# STLINK_V3EC.net
KiCad netlist of a schematic drawn in Altium Designer
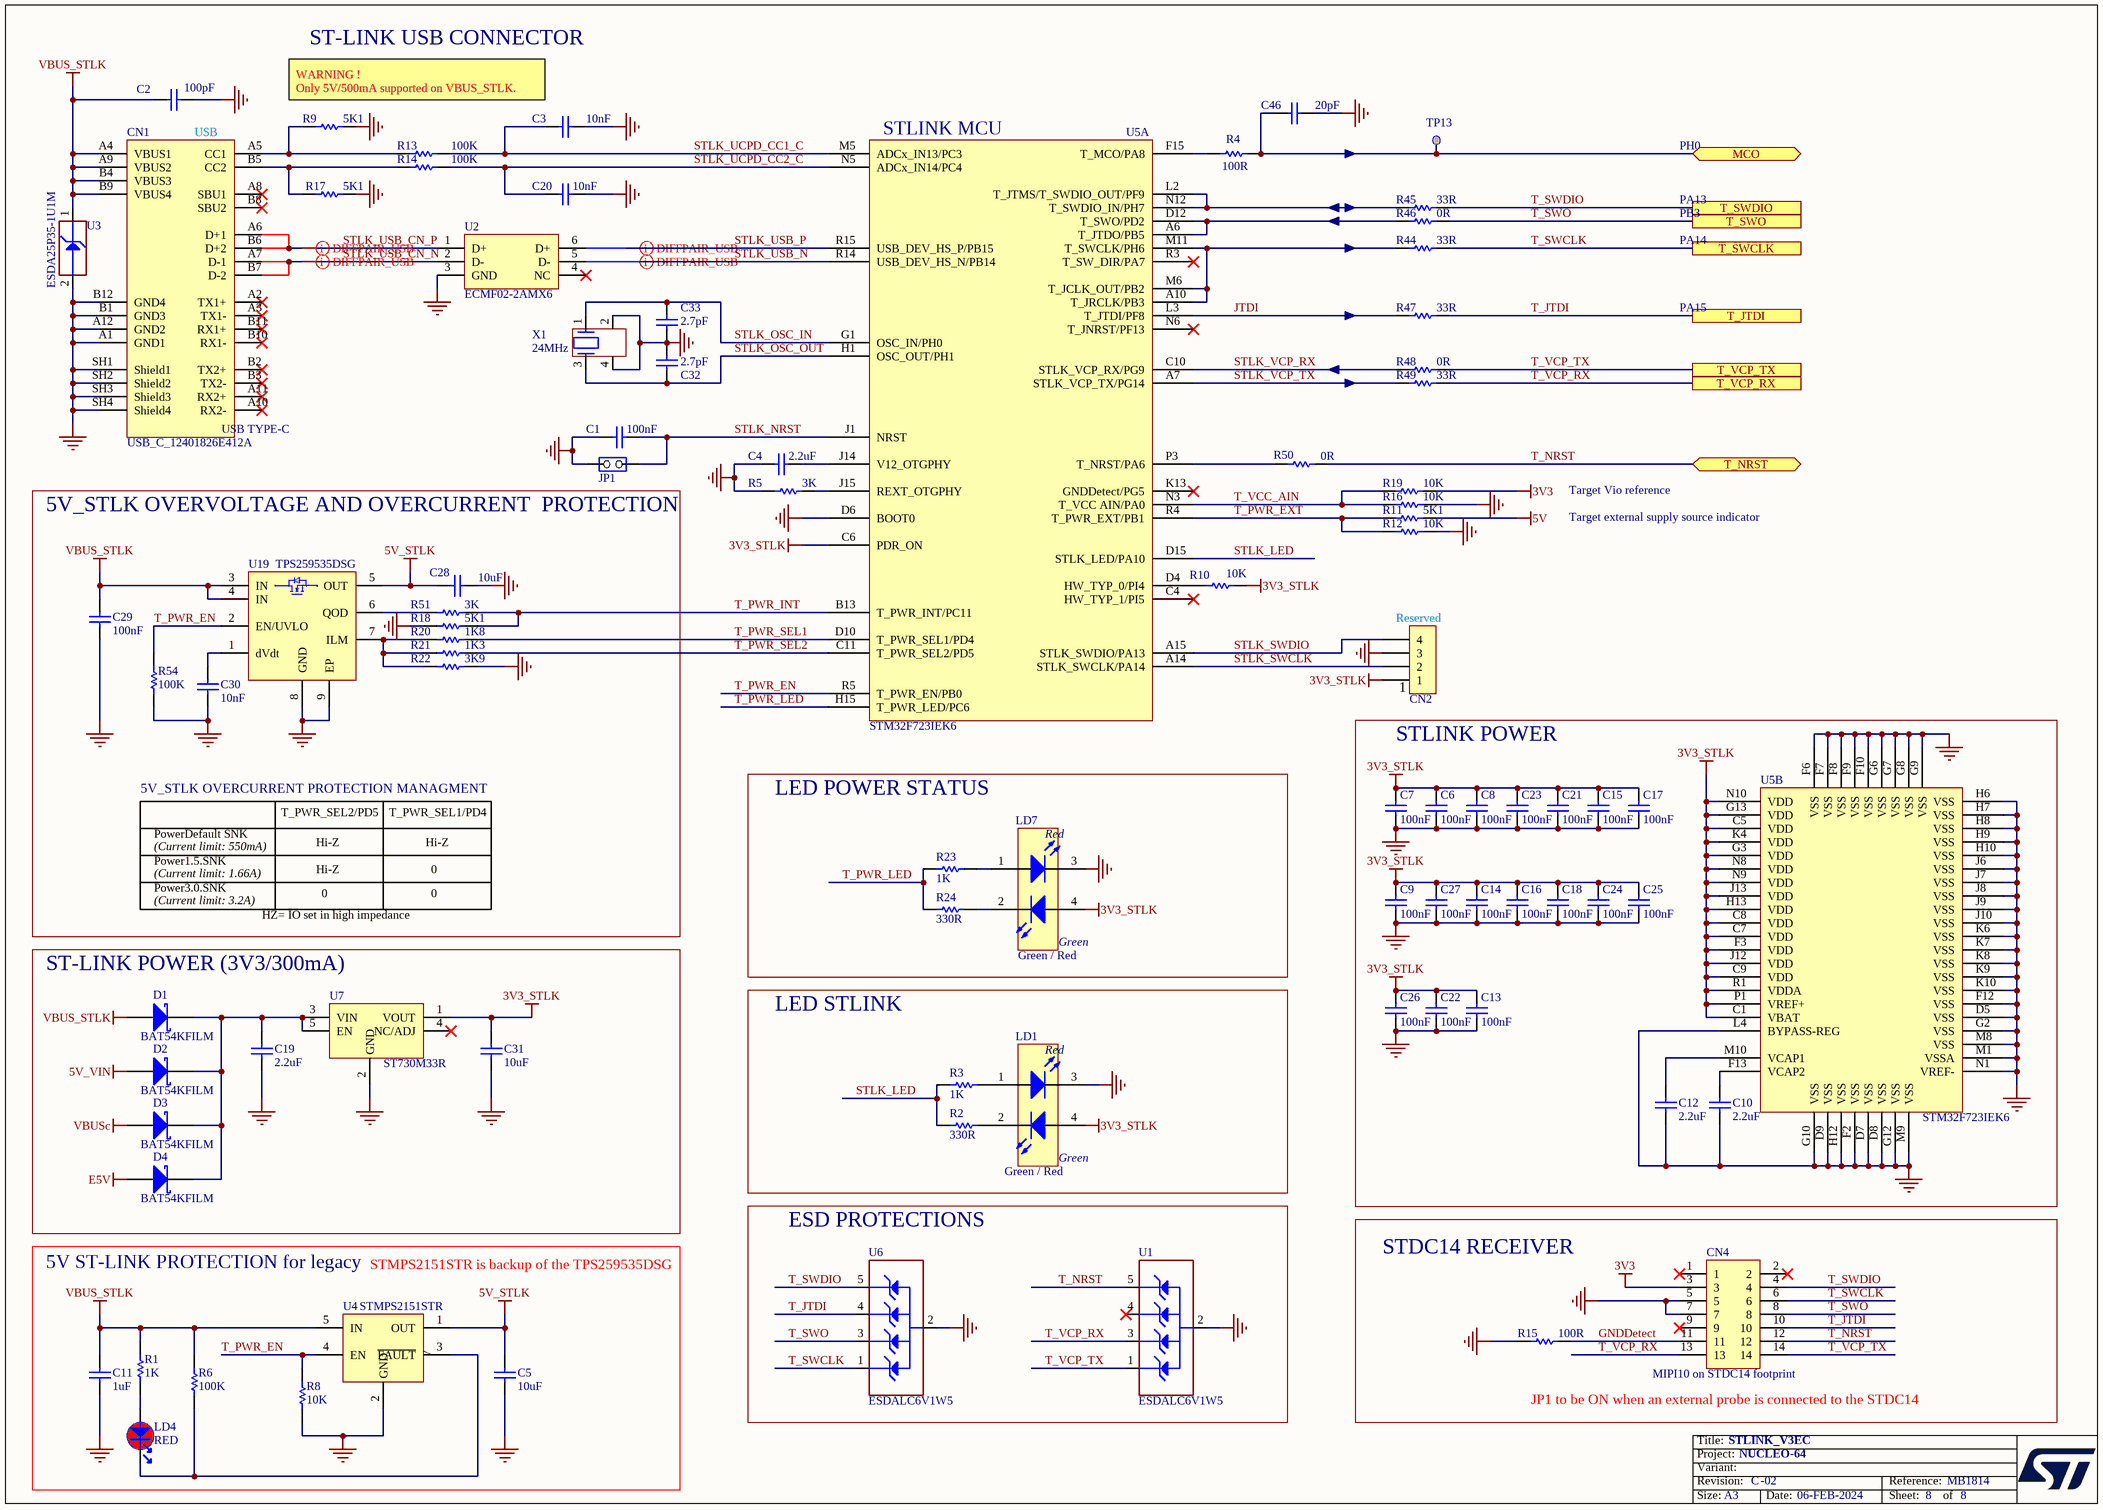
[diagram p0: STLINK_V3EC.SchDoc]

(export (version "E")
  (design (tool "Eeschema 10.0.6"))
  (components
    (comp (ref "C1")
      (value "100nF")
      (footprint "C0402")
      (description "Capacitor, MLCC, 100nF, 16V, X7R, 10%, 0402, T=0.5mm")
      (fields
        (field (name "INTERNAL_PART_NUMBER") "MCD-00006")
        (field (name "MANUFACTURER_PART_NUMBER") "CC0402KRX7R7BB104")
        (field (name "PROVIDED_BY") "SUBCO")
      )
      (libsource (lib "MCD_PARTS_database") (part "Capacitor"))
    )
    (comp (ref "C2")
      (value "100pF")
      (footprint "C0402")
      (description "Capacitor, MLCC, 100pF, 50V, NPO, +/-5%, 0402, T=0.5mm")
      (fields (field (name "INTERNAL_PART_NUMBER") "MCD-00205") (field (name "MANUFACTURER") "YAGEO"))
      (libsource (lib "MCD_PARTS_database") (part "Capacitor"))
    )
    (comp (ref "C3")
      (value "10nF")
      (footprint "C0402")
      (description "Capacitor, MLCC, 10nF, 50V, X7R, +/-10%, 0402, T=0.5mm")
      (fields (field (name "INTERNAL_PART_NUMBER") "MCD-02198") (field (name "MANUFACTURER") "YAGEO"))
      (libsource (lib "MCD_PARTS_database") (part "Capacitor"))
    )
    (comp (ref "C4")
      (value "2.2uF")
      (footprint "C0402")
      (description "Capacitor, MLCC, 2.2uF, 6.3V, X5R, +/-10%, 0402, T=0.5mm")
      (fields (field (name "INTERNAL_PART_NUMBER") "MCD-02606") (field (name "MANUFACTURER") "YAGEO"))
      (libsource (lib "MCD_PARTS_database") (part "Capacitor"))
    )
    (comp (ref "C5")
      (value "10uF")
      (footprint "C0603")
      (description "Capacitor, MLCC, 10uF, 10V, X5R, +/-10%, 0603, T=0.8mm")
      (fields (field (name "INTERNAL_PART_NUMBER") "MCD-00099") (field (name "MANUFACTURER") "MURATA"))
      (libsource (lib "MCD_PARTS_database") (part "Capacitor"))
    )
    (comp (ref "C6")
      (value "100nF")
      (footprint "C0402")
      (description "Capacitor, MLCC, 100nF, 16V, X7R, 10%, 0402, T=0.5mm")
      (fields
        (field (name "INTERNAL_PART_NUMBER") "MCD-00006")
        (field (name "MANUFACTURER_PART_NUMBER") "CC0402KRX7R7BB104")
        (field (name "PROVIDED_BY") "SUBCO")
      )
      (libsource (lib "MCD_PARTS_database") (part "Capacitor"))
    )
    (comp (ref "C7")
      (value "100nF")
      (footprint "C0402")
      (description "Capacitor, MLCC, 100nF, 16V, X7R, 10%, 0402, T=0.5mm")
      (fields
        (field (name "INTERNAL_PART_NUMBER") "MCD-00006")
        (field (name "MANUFACTURER_PART_NUMBER") "CC0402KRX7R7BB104")
        (field (name "PROVIDED_BY") "SUBCO")
      )
      (libsource (lib "MCD_PARTS_database") (part "Capacitor"))
    )
    (comp (ref "C8")
      (value "100nF")
      (footprint "C0402")
      (description "Capacitor, MLCC, 100nF, 16V, X7R, 10%, 0402, T=0.5mm")
      (fields
        (field (name "INTERNAL_PART_NUMBER") "MCD-00006")
        (field (name "MANUFACTURER_PART_NUMBER") "CC0402KRX7R7BB104")
        (field (name "PROVIDED_BY") "SUBCO")
      )
      (libsource (lib "MCD_PARTS_database") (part "Capacitor"))
    )
    (comp (ref "C9")
      (value "100nF")
      (footprint "C0402")
      (description "Capacitor, MLCC, 100nF, 16V, X7R, 10%, 0402, T=0.5mm")
      (fields
        (field (name "INTERNAL_PART_NUMBER") "MCD-00006")
        (field (name "MANUFACTURER_PART_NUMBER") "CC0402KRX7R7BB104")
        (field (name "PROVIDED_BY") "SUBCO")
      )
      (libsource (lib "MCD_PARTS_database") (part "Capacitor"))
    )
    (comp (ref "C10")
      (value "2.2uF")
      (footprint "C0402")
      (description "Capacitor, MLCC, 2.2uF, 6.3V, X5R, +/-10%, 0402, T=0.5mm")
      (fields (field (name "INTERNAL_PART_NUMBER") "MCD-02606") (field (name "MANUFACTURER") "YAGEO"))
      (libsource (lib "MCD_PARTS_database") (part "Capacitor"))
    )
    (comp (ref "C11")
      (value "1uF")
      (footprint "C0603")
      (description "Capacitor, MLCC, 1uF, 16V, X5R, 10%, 0603, T=0,8mm")
      (fields
        (field (name "INTERNAL_PART_NUMBER") "MCD-00010")
        (field (name "MANUFACTURER_PART_NUMBER") "CC0603KRX5R7BB105")
        (field (name "PROVIDED_BY") "SUBCO")
      )
      (libsource (lib "MCD_PARTS_database") (part "Capacitor"))
    )
    (comp (ref "C12")
      (value "2.2uF")
      (footprint "C0402")
      (description "Capacitor, MLCC, 2.2uF, 6.3V, X5R, +/-10%, 0402, T=0.5mm")
      (fields (field (name "INTERNAL_PART_NUMBER") "MCD-02606") (field (name "MANUFACTURER") "YAGEO"))
      (libsource (lib "MCD_PARTS_database") (part "Capacitor"))
    )
    (comp (ref "C13")
      (value "100nF")
      (footprint "C0402")
      (description "Capacitor, MLCC, 100nF, 16V, X7R, 10%, 0402, T=0.5mm")
      (fields
        (field (name "INTERNAL_PART_NUMBER") "MCD-00006")
        (field (name "MANUFACTURER_PART_NUMBER") "CC0402KRX7R7BB104")
        (field (name "PROVIDED_BY") "SUBCO")
      )
      (libsource (lib "MCD_PARTS_database") (part "Capacitor"))
    )
    (comp (ref "C14")
      (value "100nF")
      (footprint "C0402")
      (description "Capacitor, MLCC, 100nF, 16V, X7R, 10%, 0402, T=0.5mm")
      (fields
        (field (name "INTERNAL_PART_NUMBER") "MCD-00006")
        (field (name "MANUFACTURER_PART_NUMBER") "CC0402KRX7R7BB104")
        (field (name "PROVIDED_BY") "SUBCO")
      )
      (libsource (lib "MCD_PARTS_database") (part "Capacitor"))
    )
    (comp (ref "C15")
      (value "100nF")
      (footprint "C0402")
      (description "Capacitor, MLCC, 100nF, 16V, X7R, 10%, 0402, T=0.5mm")
      (fields
        (field (name "INTERNAL_PART_NUMBER") "MCD-00006")
        (field (name "MANUFACTURER_PART_NUMBER") "CC0402KRX7R7BB104")
        (field (name "PROVIDED_BY") "SUBCO")
      )
      (libsource (lib "MCD_PARTS_database") (part "Capacitor"))
    )
    (comp (ref "C16")
      (value "100nF")
      (footprint "C0402")
      (description "Capacitor, MLCC, 100nF, 16V, X7R, 10%, 0402, T=0.5mm")
      (fields
        (field (name "INTERNAL_PART_NUMBER") "MCD-00006")
        (field (name "MANUFACTURER_PART_NUMBER") "CC0402KRX7R7BB104")
        (field (name "PROVIDED_BY") "SUBCO")
      )
      (libsource (lib "MCD_PARTS_database") (part "Capacitor"))
    )
    (comp (ref "C17")
      (value "100nF")
      (footprint "C0402")
      (description "Capacitor, MLCC, 100nF, 16V, X7R, 10%, 0402, T=0.5mm")
      (fields
        (field (name "INTERNAL_PART_NUMBER") "MCD-00006")
        (field (name "MANUFACTURER_PART_NUMBER") "CC0402KRX7R7BB104")
        (field (name "PROVIDED_BY") "SUBCO")
      )
      (libsource (lib "MCD_PARTS_database") (part "Capacitor"))
    )
    (comp (ref "C18")
      (value "100nF")
      (footprint "C0402")
      (description "Capacitor, MLCC, 100nF, 16V, X7R, 10%, 0402, T=0.5mm")
      (fields
        (field (name "INTERNAL_PART_NUMBER") "MCD-00006")
        (field (name "MANUFACTURER_PART_NUMBER") "CC0402KRX7R7BB104")
        (field (name "PROVIDED_BY") "SUBCO")
      )
      (libsource (lib "MCD_PARTS_database") (part "Capacitor"))
    )
    (comp (ref "C19")
      (value "2.2uF")
      (footprint "C0805")
      (description "Capacitor, MLCC, 2.2uF, 25V, X7R, +/-10%, 0805, T=1,25mm")
      (fields
        (field (name "INTERNAL_PART_NUMBER") "MCD-02372")
        (field (name "MANUFACTURER_PART_NUMBER") "GRM21BR71E225KE11L")
        (field (name "PROVIDED_BY") "SUBCO")
      )
      (libsource (lib "MCD_PARTS_database") (part "Capacitor"))
    )
    (comp (ref "C20")
      (value "10nF")
      (footprint "C0402")
      (description "Capacitor, MLCC, 10nF, 50V, X7R, +/-10%, 0402, T=0.5mm")
      (fields (field (name "INTERNAL_PART_NUMBER") "MCD-02198") (field (name "MANUFACTURER") "YAGEO"))
      (libsource (lib "MCD_PARTS_database") (part "Capacitor"))
    )
    (comp (ref "C21")
      (value "100nF")
      (footprint "C0402")
      (description "Capacitor, MLCC, 100nF, 16V, X7R, 10%, 0402, T=0.5mm")
      (fields
        (field (name "INTERNAL_PART_NUMBER") "MCD-00006")
        (field (name "MANUFACTURER_PART_NUMBER") "CC0402KRX7R7BB104")
        (field (name "PROVIDED_BY") "SUBCO")
      )
      (libsource (lib "MCD_PARTS_database") (part "Capacitor"))
    )
    (comp (ref "C22")
      (value "100nF")
      (footprint "C0402")
      (description "Capacitor, MLCC, 100nF, 16V, X7R, 10%, 0402, T=0.5mm")
      (fields
        (field (name "INTERNAL_PART_NUMBER") "MCD-00006")
        (field (name "MANUFACTURER_PART_NUMBER") "CC0402KRX7R7BB104")
        (field (name "PROVIDED_BY") "SUBCO")
      )
      (libsource (lib "MCD_PARTS_database") (part "Capacitor"))
    )
    (comp (ref "C23")
      (value "100nF")
      (footprint "C0402")
      (description "Capacitor, MLCC, 100nF, 16V, X7R, 10%, 0402, T=0.5mm")
      (fields
        (field (name "INTERNAL_PART_NUMBER") "MCD-00006")
        (field (name "MANUFACTURER_PART_NUMBER") "CC0402KRX7R7BB104")
        (field (name "PROVIDED_BY") "SUBCO")
      )
      (libsource (lib "MCD_PARTS_database") (part "Capacitor"))
    )
    (comp (ref "C24")
      (value "100nF")
      (footprint "C0402")
      (description "Capacitor, MLCC, 100nF, 16V, X7R, 10%, 0402, T=0.5mm")
      (fields
        (field (name "INTERNAL_PART_NUMBER") "MCD-00006")
        (field (name "MANUFACTURER_PART_NUMBER") "CC0402KRX7R7BB104")
        (field (name "PROVIDED_BY") "SUBCO")
      )
      (libsource (lib "MCD_PARTS_database") (part "Capacitor"))
    )
    (comp (ref "C25")
      (value "100nF")
      (footprint "C0402")
      (description "Capacitor, MLCC, 100nF, 16V, X7R, 10%, 0402, T=0.5mm")
      (fields
        (field (name "INTERNAL_PART_NUMBER") "MCD-00006")
        (field (name "MANUFACTURER_PART_NUMBER") "CC0402KRX7R7BB104")
        (field (name "PROVIDED_BY") "SUBCO")
      )
      (libsource (lib "MCD_PARTS_database") (part "Capacitor"))
    )
    (comp (ref "C26")
      (value "100nF")
      (footprint "C0402")
      (description "Capacitor, MLCC, 100nF, 16V, X7R, 10%, 0402, T=0.5mm")
      (fields
        (field (name "INTERNAL_PART_NUMBER") "MCD-00006")
        (field (name "MANUFACTURER_PART_NUMBER") "CC0402KRX7R7BB104")
        (field (name "PROVIDED_BY") "SUBCO")
      )
      (libsource (lib "MCD_PARTS_database") (part "Capacitor"))
    )
    (comp (ref "C27")
      (value "100nF")
      (footprint "C0402")
      (description "Capacitor, MLCC, 100nF, 16V, X7R, 10%, 0402, T=0.5mm")
      (fields
        (field (name "INTERNAL_PART_NUMBER") "MCD-00006")
        (field (name "MANUFACTURER_PART_NUMBER") "CC0402KRX7R7BB104")
        (field (name "PROVIDED_BY") "SUBCO")
      )
      (libsource (lib "MCD_PARTS_database") (part "Capacitor"))
    )
    (comp (ref "C28")
      (value "10uF")
      (footprint "C0603")
      (description "Capacitor, MLCC, 10uF, 10V, X5R, +/-10%, 0603, T=0.8mm")
      (fields (field (name "INTERNAL_PART_NUMBER") "MCD-00099") (field (name "MANUFACTURER") "MURATA"))
      (libsource (lib "MCD_PARTS_database") (part "Capacitor"))
    )
    (comp (ref "C29")
      (value "100nF")
      (footprint "C0402")
      (description "Capacitor, MLCC, 100nF, 25V, X7R, +/-10%, 0402, T=0.5mm")
      (fields (field (name "INTERNAL_PART_NUMBER") "MCD-02355") (field (name "MANUFACTURER") "WALSIN"))
      (libsource (lib "MCD_PARTS_database") (part "Capacitor"))
    )
    (comp (ref "C30")
      (value "10nF")
      (footprint "C0402")
      (description "Capacitor, MLCC, 10nF, 50V, X7R, +/-10%, 0402, T=0.5mm")
      (fields (field (name "INTERNAL_PART_NUMBER") "MCD-02198") (field (name "MANUFACTURER") "YAGEO"))
      (libsource (lib "MCD_PARTS_database") (part "Capacitor"))
    )
    (comp (ref "C31")
      (value "10uF")
      (footprint "C0603")
      (description "Capacitor, MLCC, 10uF, 10V, X5R, +/-10%, 0603, T=0.8mm")
      (fields (field (name "INTERNAL_PART_NUMBER") "MCD-00099") (field (name "MANUFACTURER") "MURATA"))
      (libsource (lib "MCD_PARTS_database") (part "Capacitor"))
    )
    (comp (ref "C32")
      (value "2.7pF")
      (footprint "C0402")
      (description "Capacitor, MLCC, 2.7pF, 50V, NPO, +/-0.1pF, 0402, T=0.5mm")
      (fields (field (name "INTERNAL_PART_NUMBER") "MCD-01774") (field (name "MANUFACTURER") "YAGEO"))
      (libsource (lib "MCD_PARTS_database") (part "Capacitor"))
    )
    (comp (ref "C33")
      (value "2.7pF")
      (footprint "C0402")
      (description "Capacitor, MLCC, 2.7pF, 50V, NPO, +/-0.1pF, 0402, T=0.5mm")
      (fields (field (name "INTERNAL_PART_NUMBER") "MCD-01774") (field (name "MANUFACTURER") "YAGEO"))
      (libsource (lib "MCD_PARTS_database") (part "Capacitor"))
    )
    (comp (ref "C46")
      (value "20pF")
      (footprint "C0402")
      (description "Capacitor, MLCC, 20pF, 50V, NPO, +/- 5%, 0402, T=0.5mm")
      (fields (field (name "INTERNAL_PART_NUMBER") "MCD-00016") (field (name "MANUFACTURER") "YAGEO"))
      (libsource (lib "MCD_PARTS_database") (part "Capacitor"))
    )
    (comp (ref "CN1")
      (value "USB_C_12401826E412A")
      (footprint "CON_USB-TYPEC_AMPHENOL_12401826E412A")
      (description "USB_TypeC, 24 pins, RA, SMD, T=2.96mm")
      (fields (field (name "INTERNAL_PART_NUMBER") "MCD-03232") (field (name "MANUFACTURER") "AMPHENOL ICC"))
      (libsource (lib "MCD_PARTS_database") (part "USB_TYPE_C_Receptacle"))
    )
    (comp (ref "CN2")
      (value "Header 4x1")
      (footprint "CON_SAMTEC_TSW-104-07-G-S")
      (description "Header, 4x1, 2,54mm, VR, TH, Height 5.84mm/2.54mm")
      (fields
        (field (name "INTERNAL_PART_NUMBER") "MCD-00029")
        (field (name "MANUFACTURER_PART_NUMBER") "TSW-104-07-x-S")
        (field (name "PROVIDED_BY") "SUBCO")
      )
      (libsource (lib "MCD_PARTS_database") (part "Header 4x1"))
    )
    (comp (ref "CN4")
      (value "Header 7x2")
      (footprint "CON_STDC14_Receiver_MEDIUM_WITH_MIPI10_3D")
      (description "Header, 5x2, 1.27mm, VR, SMD, T=5.97mm/3.05mm")
      (fields (field (name "INTERNAL_PART_NUMBER") "MCD-01226") (field (name "MANUFACTURER") "SAMTEC"))
      (libsource (lib "MCD_PARTS_database") (part "Header 7x2"))
    )
    (comp (ref "D1")
      (value "BAT54KFILM")
      (footprint "DIO_SOD523_1A_2K")
      (description "Small signal Schottky diodes")
      (fields (field (name "INTERNAL_PART_NUMBER") "MCD-01677") (field (name "BMS_PART_NUMBER") "9151123"))
      (libsource (lib "MCD_PARTS_database") (part "SCHOTTKY_1A_2K"))
    )
    (comp (ref "D2")
      (value "BAT54KFILM")
      (footprint "DIO_SOD523_1A_2K")
      (description "Small signal Schottky diodes")
      (fields (field (name "INTERNAL_PART_NUMBER") "MCD-01677") (field (name "BMS_PART_NUMBER") "9151123"))
      (libsource (lib "MCD_PARTS_database") (part "SCHOTTKY_1A_2K"))
    )
    (comp (ref "D3")
      (value "BAT54KFILM")
      (footprint "DIO_SOD523_1A_2K")
      (description "Small signal Schottky diodes")
      (fields (field (name "INTERNAL_PART_NUMBER") "MCD-01677") (field (name "BMS_PART_NUMBER") "9151123"))
      (libsource (lib "MCD_PARTS_database") (part "SCHOTTKY_1A_2K"))
    )
    (comp (ref "D4")
      (value "BAT54KFILM")
      (footprint "DIO_SOD523_1A_2K")
      (description "Small signal Schottky diodes")
      (fields (field (name "INTERNAL_PART_NUMBER") "MCD-01677") (field (name "BMS_PART_NUMBER") "9151123"))
      (libsource (lib "MCD_PARTS_database") (part "SCHOTTKY_1A_2K"))
    )
    (comp (ref "JP1")
      (value "Jumper_Header 2x1")
      (footprint "CON_SAMTEC_TSW-102-07-G-S")
      (description "Header, 2x1, 2,54mm, VR, TH, Height 5.84mm/2.54mm")
      (fields (field (name "INTERNAL_PART_NUMBER") "MCD-00045") (field (name "MANUFACTURER") "SAMTEC"))
      (libsource (lib "MCD_PARTS_database") (part "Jumper_Header 2x1"))
    )
    (comp (ref "LD1")
      (value "Green / Red")
      (footprint "LED_BI-GR_WE-150141SV73110")
      (description "LED Bicolor, Green/Red, 2V, 20mA,  4-PLCC")
      (fields
        (field (name "INTERNAL_PART_NUMBER") "MCD-02631")
        (field (name "MANUFACTURER") "WURTH ELEKTRONIK")
      )
      (libsource (lib "MCD_PARTS_database") (part "LED_BICOLOR"))
    )
    (comp (ref "LD4")
      (value "RED")
      (footprint "LED_0603_VISHAY_VLMS1300-GS08_RED_1A2K_H0P8")
      (description "LED Red, 0603 SMD, 2V Forward Voltage")
      (fields
        (field (name "INTERNAL_PART_NUMBER") "MCD-00587")
        (field (name "MANUFACTURER_PART_NUMBER") "VLMS1300-GS08")
        (field (name "PROVIDED_BY") "SUBCO")
      )
      (libsource (lib "MCD_PARTS_database") (part "LED_red"))
    )
    (comp (ref "LD7")
      (value "Green / Red")
      (footprint "LED_BI-GR_WE-150141SV73110")
      (description "LED Bicolor, Green/Red, 2V, 20mA,  4-PLCC")
      (fields
        (field (name "INTERNAL_PART_NUMBER") "MCD-02631")
        (field (name "MANUFACTURER") "WURTH ELEKTRONIK")
      )
      (libsource (lib "MCD_PARTS_database") (part "LED_BICOLOR"))
    )
    (comp (ref "R1")
      (value "1K")
      (footprint "R0402")
      (description "Resistor,1K,0402,1%,1/16W")
      (fields
        (field (name "INTERNAL_PART_NUMBER") "MCD-00061")
        (field (name "MANUFACTURER_PART_NUMBER") "RC0402FR-071KL")
        (field (name "PROVIDED_BY") "SUBCO")
      )
      (libsource (lib "MCD_PARTS_database") (part "Resistor"))
    )
    (comp (ref "R2")
      (value "330R")
      (footprint "R0402")
      (description "Resistor, 330R, 0402, +/-1%, 1/16W")
      (fields (field (name "INTERNAL_PART_NUMBER") "MCD-00062") (field (name "MANUFACTURER") "YAGEO"))
      (libsource (lib "MCD_PARTS_database") (part "Resistor"))
    )
    (comp (ref "R3")
      (value "1K")
      (footprint "R0402")
      (description "Resistor, 1K, 0402, +/-0.1%, 1/16W, +/-25ppm/°C")
      (fields (field (name "INTERNAL_PART_NUMBER") "MCD-02665") (field (name "MANUFACTURER") "YAGEO"))
      (libsource (lib "MCD_PARTS_database") (part "Resistor"))
    )
    (comp (ref "R4")
      (value "100R")
      (footprint "R0402")
      (description "Resistor, 100R, 0402, +/- 1%, 1/16W")
      (fields (field (name "INTERNAL_PART_NUMBER") "MCD-00067") (field (name "MANUFACTURER") "YAGEO"))
      (libsource (lib "MCD_PARTS_database") (part "Resistor"))
    )
    (comp (ref "R5")
      (value "3K")
      (footprint "R0402")
      (description "Resistor,3K,0402,1%,1/16W")
      (fields
        (field (name "INTERNAL_PART_NUMBER") "MCD-00185")
        (field (name "MANUFACTURER_PART_NUMBER") "RC0402FR-073KL")
        (field (name "PROVIDED_BY") "SUBCO")
      )
      (libsource (lib "MCD_PARTS_database") (part "Resistor"))
    )
    (comp (ref "R6")
      (value "100K")
      (footprint "R0402")
      (description "Resistor,100K,0402,1%,1/16W")
      (fields
        (field (name "INTERNAL_PART_NUMBER") "MCD-00059")
        (field (name "MANUFACTURER_PART_NUMBER") "RC0402FR-07100KL")
        (field (name "PROVIDED_BY") "SUBCO")
      )
      (libsource (lib "MCD_PARTS_database") (part "Resistor"))
    )
    (comp (ref "R8")
      (value "10K")
      (footprint "R0402")
      (description "Resistor,10K,0402,1%,1/16W")
      (fields
        (field (name "INTERNAL_PART_NUMBER") "MCD-00053")
        (field (name "MANUFACTURER_PART_NUMBER") "RC0402FR-0710KL")
        (field (name "PROVIDED_BY") "SUBCO")
      )
      (libsource (lib "MCD_PARTS_database") (part "Resistor"))
    )
    (comp (ref "R9")
      (value "5K1")
      (footprint "R0402")
      (description "Resistor, 5K1, 0402, +/-1%, 1/16W")
      (fields (field (name "INTERNAL_PART_NUMBER") "MCD-00333") (field (name "MANUFACTURER") "YAGEO"))
      (libsource (lib "MCD_PARTS_database") (part "Resistor"))
    )
    (comp (ref "R10")
      (value "10K")
      (footprint "R0402")
      (description "Resistor,10K,0402,1%,1/16W")
      (fields
        (field (name "INTERNAL_PART_NUMBER") "MCD-00053")
        (field (name "MANUFACTURER_PART_NUMBER") "RC0402FR-0710KL")
        (field (name "PROVIDED_BY") "SUBCO")
      )
      (libsource (lib "MCD_PARTS_database") (part "Resistor"))
    )
    (comp (ref "R11")
      (value "5K1")
      (footprint "R0402")
      (description "Resistor, 5K1, 0402, +/-1%, 1/16W")
      (fields (field (name "INTERNAL_PART_NUMBER") "MCD-00333") (field (name "MANUFACTURER") "YAGEO"))
      (libsource (lib "MCD_PARTS_database") (part "Resistor"))
    )
    (comp (ref "R12")
      (value "10K")
      (footprint "R0402")
      (description "Resistor, 10K, 0402, +/-1%, 1/16W")
      (fields (field (name "INTERNAL_PART_NUMBER") "MCD-00053") (field (name "BMS_PART_NUMBER") "9131590"))
      (libsource (lib "MCD_PARTS_database") (part "Resistor"))
    )
    (comp (ref "R13")
      (value "100K")
      (footprint "R0402")
      (description "Resistor, 100K, 0402, +/-1%, 1/16W")
      (fields (field (name "INTERNAL_PART_NUMBER") "MCD-00059") (field (name "MANUFACTURER") "YAGEO"))
      (libsource (lib "MCD_PARTS_database") (part "Resistor"))
    )
    (comp (ref "R14")
      (value "100K")
      (footprint "R0402")
      (description "Resistor, 100K, 0402, +/-1%, 1/16W")
      (fields (field (name "INTERNAL_PART_NUMBER") "MCD-00059") (field (name "MANUFACTURER") "YAGEO"))
      (libsource (lib "MCD_PARTS_database") (part "Resistor"))
    )
    (comp (ref "R15")
      (value "100R")
      (footprint "R0402")
      (description "Resistor, 100R, 0402, +/- 1%, 1/16W")
      (fields (field (name "INTERNAL_PART_NUMBER") "MCD-00067") (field (name "MANUFACTURER") "YAGEO"))
      (libsource (lib "MCD_PARTS_database") (part "Resistor"))
    )
    (comp (ref "R16")
      (value "10K")
      (footprint "R0402")
      (description "Resistor, 10K, 0402, +/-1%, 1/16W")
      (fields (field (name "INTERNAL_PART_NUMBER") "MCD-00053") (field (name "BMS_PART_NUMBER") "9131590"))
      (libsource (lib "MCD_PARTS_database") (part "Resistor"))
    )
    (comp (ref "R17")
      (value "5K1")
      (footprint "R0402")
      (description "Resistor, 5K1, 0402, +/-1%, 1/16W")
      (fields (field (name "INTERNAL_PART_NUMBER") "MCD-00333") (field (name "MANUFACTURER") "YAGEO"))
      (libsource (lib "MCD_PARTS_database") (part "Resistor"))
    )
    (comp (ref "R18")
      (value "5K1")
      (footprint "R0402")
      (description "Resistor, 5K1, 0402, +/-1%, 1/16W")
      (fields (field (name "INTERNAL_PART_NUMBER") "MCD-00333") (field (name "MANUFACTURER") "YAGEO"))
      (libsource (lib "MCD_PARTS_database") (part "Resistor"))
    )
    (comp (ref "R19")
      (value "10K")
      (footprint "R0402")
      (description "Resistor, 10K, 0402, +/-1%, 1/16W")
      (fields (field (name "INTERNAL_PART_NUMBER") "MCD-00053") (field (name "BMS_PART_NUMBER") "9131590"))
      (libsource (lib "MCD_PARTS_database") (part "Resistor"))
    )
    (comp (ref "R20")
      (value "1K8")
      (footprint "R0402")
      (description "Resistor, 1K8, 0402, +/-1%, 1/16W")
      (fields (field (name "INTERNAL_PART_NUMBER") "MCD-00409") (field (name "MANUFACTURER") "YAGEO"))
      (libsource (lib "MCD_PARTS_database") (part "Resistor"))
    )
    (comp (ref "R21")
      (value "1K3")
      (footprint "R0402")
      (description "Resistor, 1K3, 0402, +/-1%, 1/16W")
      (fields (field (name "INTERNAL_PART_NUMBER") "MCD-00381") (field (name "MANUFACTURER") "YAGEO"))
      (libsource (lib "MCD_PARTS_database") (part "Resistor"))
    )
    (comp (ref "R22")
      (value "3K9")
      (footprint "R0402")
      (description "Resistor, 3K9, 0402, +/-1%, 1/16W, +/-100ppm/°C")
      (fields (field (name "INTERNAL_PART_NUMBER") "MCD-02455") (field (name "MANUFACTURER") "YAGEO"))
      (libsource (lib "MCD_PARTS_database") (part "Resistor"))
    )
    (comp (ref "R23")
      (value "1K")
      (footprint "R0402")
      (description "Resistor, 1K, 0402, +/-0.1%, 1/16W, +/-25ppm/°C")
      (fields (field (name "INTERNAL_PART_NUMBER") "MCD-02665") (field (name "MANUFACTURER") "YAGEO"))
      (libsource (lib "MCD_PARTS_database") (part "Resistor"))
    )
    (comp (ref "R24")
      (value "330R")
      (footprint "R0402")
      (description "Resistor, 330R, 0402, +/-1%, 1/16W")
      (fields (field (name "INTERNAL_PART_NUMBER") "MCD-00062") (field (name "MANUFACTURER") "YAGEO"))
      (libsource (lib "MCD_PARTS_database") (part "Resistor"))
    )
    (comp (ref "R44")
      (value "33R")
      (footprint "R0402")
      (description "Resistor, 33R, 0402, +/-1%, 1/16W")
      (fields (field (name "INTERNAL_PART_NUMBER") "MCD-00455") (field (name "MANUFACTURER") "YAGEO"))
      (libsource (lib "MCD_PARTS_database") (part "Resistor"))
    )
    (comp (ref "R45")
      (value "33R")
      (footprint "R0402")
      (description "Resistor, 33R, 0402, +/-1%, 1/16W")
      (fields (field (name "INTERNAL_PART_NUMBER") "MCD-00455") (field (name "MANUFACTURER") "YAGEO"))
      (libsource (lib "MCD_PARTS_database") (part "Resistor"))
    )
    (comp (ref "R46")
      (value "0R")
      (footprint "R0402")
      (description "Resistor, 0R, 0402, +/-5%, 1/16W")
      (fields (field (name "INTERNAL_PART_NUMBER") "MCD-00052") (field (name "MANUFACTURER") "YAGEO"))
      (libsource (lib "MCD_PARTS_database") (part "Resistor"))
    )
    (comp (ref "R47")
      (value "33R")
      (footprint "R0402")
      (description "Resistor, 33R, 0402, +/-1%, 1/16W")
      (fields (field (name "INTERNAL_PART_NUMBER") "MCD-00455") (field (name "MANUFACTURER") "YAGEO"))
      (libsource (lib "MCD_PARTS_database") (part "Resistor"))
    )
    (comp (ref "R48")
      (value "0R")
      (footprint "R0402")
      (description "Resistor, 0R, 0402, +/-5%, 1/16W")
      (fields (field (name "INTERNAL_PART_NUMBER") "MCD-00052") (field (name "MANUFACTURER") "YAGEO"))
      (libsource (lib "MCD_PARTS_database") (part "Resistor"))
    )
    (comp (ref "R49")
      (value "33R")
      (footprint "R0402")
      (description "Resistor, 33R, 0402, +/-1%, 1/16W")
      (fields (field (name "INTERNAL_PART_NUMBER") "MCD-00455") (field (name "MANUFACTURER") "YAGEO"))
      (libsource (lib "MCD_PARTS_database") (part "Resistor"))
    )
    (comp (ref "R50")
      (value "0R")
      (footprint "R0402")
      (description "Resistor, 0R, 0402, +/-5%, 1/16W")
      (fields (field (name "INTERNAL_PART_NUMBER") "MCD-00052") (field (name "MANUFACTURER") "YAGEO"))
      (libsource (lib "MCD_PARTS_database") (part "Resistor"))
    )
    (comp (ref "R51")
      (value "3K")
      (footprint "R0402")
      (description "Resistor, 3K, 0402, +/-1%, 1/16W")
      (fields (field (name "INTERNAL_PART_NUMBER") "MCD-00185") (field (name "MANUFACTURER") "YAGEO"))
      (libsource (lib "MCD_PARTS_database") (part "Resistor"))
    )
    (comp (ref "R54")
      (value "100K")
      (footprint "R0402")
      (description "Resistor,100K,0402,1%,1/16W")
      (fields
        (field (name "INTERNAL_PART_NUMBER") "MCD-00059")
        (field (name "MANUFACTURER_PART_NUMBER") "RC0402FR-07100KL")
        (field (name "PROVIDED_BY") "SUBCO")
      )
      (libsource (lib "MCD_PARTS_database") (part "Resistor"))
    )
    (comp (ref "TP13")
      (value "Test Point")
      (footprint "TP_SMD_1MM")
      (description "Test Point 1mm")
      (fields
        (field (name "INTERNAL_PART_NUMBER") "MCD-00074")
        (field (name "MANUFACTURER_PART_NUMBER") "n/a")
      )
      (libsource (lib "MCD_PARTS_database") (part "Test Point"))
    )
    (comp (ref "U1")
      (value "ESDALC6V1W5")
      (footprint "ESD_SOT323-5L")
      (description "Dual Transil array for ESD protection")
      (fields (field (name "INTERNAL_PART_NUMBER") "MCD-00136") (field (name "BMS_PART_NUMBER") "9151112"))
      (libsource (lib "MCD_PARTS_database") (part "ESDALC6V1W5"))
    )
    (comp (ref "U2")
      (value "ECMF02-2AMX6")
      (footprint "ESD_QFN-6L_1P7X1P5_P050")
      (description "Common mode filter with ESD protection for USB 2.0 interface")
      (fields (field (name "INTERNAL_PART_NUMBER") "MCD-00649") (field (name "BMS_PART_NUMBER") "9151138"))
      (libsource (lib "MCD_PARTS_database") (part "ECMF02-2AMX6"))
    )
    (comp (ref "U3")
      (value "ESDA25P35-1U1M")
      (footprint "ESD_QFN1610_2N_1K_2A")
      (description "High power Transient voltage suppressor:25V/35A EOS and ESD transients protection.")
      (fields
        (field (name "INTERNAL_PART_NUMBER") "MCD-01207")
        (field (name "MANUFACTURER") "STMICROELECTRONICS")
        (field (name "PROVIDED_BY") "SUBCO with ST control")
      )
      (libsource (lib "MCD_PARTS_database") (part "ESD-TRANSIL"))
    )
    (comp (ref "U4")
      (value "STMPS2151STR")
      (footprint "MOS_SOT23-5L")
      (description "500mA, Enhanced single channel power switches with active high enable pin")
      (fields
        (field (name "INTERNAL_PART_NUMBER") "MCD-00159")
        (field (name "MANUFACTURER") "STMICROELECTRONICS")
        (field (name "PROVIDED_BY") "Subcon")
      )
      (libsource (lib "MCD_PARTS_database") (part "STMPS2151STR"))
    )
    (comp (ref "U5")
      (value "STM32F723IEK6")
      (footprint "ICC_UFBGA201_176+25_10X10_P065")
      (description "STM32F723IEK  (STM32F7) BGA176")
      (fields (field (name "INTERNAL_PART_NUMBER") "MCD-02706") (field (name "BMS_PART_NUMBER") "9175300"))
      (libsource (lib "MCD_PARTS_database") (part "STLINK-V3EC"))
    )
    (comp (ref "U6")
      (value "ESDALC6V1W5")
      (footprint "ESD_SOT323-5L")
      (description "Dual Transil array for ESD protection")
      (fields (field (name "INTERNAL_PART_NUMBER") "MCD-00136") (field (name "BMS_PART_NUMBER") "9151112"))
      (libsource (lib "MCD_PARTS_database") (part "ESDALC6V1W5"))
    )
    (comp (ref "U7")
      (value "ST730M33R")
      (footprint "ICC_SOT23-5L_H1P45")
      (description "LDO, 3.3V, 300mA, High input voltage: 2.5V to 28V, SOT23-5L")
      (fields
        (field (name "INTERNAL_PART_NUMBER") "MCD-02514")
        (field (name "MANUFACTURER") "STMICROELECTRONICS")
      )
      (libsource (lib "MCD_PARTS_database") (part "ST730M33R"))
    )
    (comp (ref "U19")
      (value "TPS259535DSG")
      (footprint "ICC_WSON8-EPAD_2X2_P050")
      (description "eFuse with Fast Overvoltage Protection 2.7V to 18V 4A 34mOhm 8-Pin WSON")
      (fields
        (field (name "INTERNAL_PART_NUMBER") "MCD-02532")
        (field (name "MANUFACTURER") "TEXAS INSTRUMENTS")
      )
      (libsource (lib "MCD_PARTS_database") (part "TPS259535DSG"))
    )
    (comp (ref "X1")
      (value "24MHz")
      (footprint "CRY_NX2016SA_4P")
      (description "Crystal, 24MHz, 6pF, +/-20ppm, 80R, 2x1.6mm")
      (fields (field (name "INTERNAL_PART_NUMBER") "MCD-01036") (field (name "BMS_PART_NUMBER") "9157045"))
      (libsource (lib "MCD_PARTS_database") (part "XTAL_4_PINS"))
    )
  )
  (nets
    (net (code "1") (name "/GNDDetect") (class "Default")
      (node (ref "CN4") (pin "11") (pinfunction "11_11") (pintype "passive"))
      (node (ref "R15") (pin "2") (pinfunction "2_2") (pintype "passive"))
    )
    (net (code "2") (name "/JTDI") (class "Default")
      (node (ref "R47") (pin "1") (pinfunction "1_1") (pintype "passive"))
      (node (ref "U5") (pin "L3") (pinfunction "T_JTDI/PF8_L3") (pintype "passive"))
    )
    (net (code "3") (name "/MCO") (class "Default")
      (node (ref "C46") (pin "2") (pinfunction "2_2") (pintype "passive"))
      (node (ref "R4") (pin "2") (pinfunction "2_2") (pintype "passive"))
      (node (ref "TP13") (pin "1") (pinfunction "1_1") (pintype "passive"))
    )
    (net (code "4") (name "/STLK_LED") (class "Default")
      (node (ref "R2") (pin "1") (pinfunction "1_1") (pintype "passive"))
      (node (ref "R3") (pin "2") (pinfunction "2_2") (pintype "passive"))
      (node (ref "U5") (pin "D15") (pinfunction "STLK_LED/PA10_D15") (pintype "passive"))
    )
    (net (code "5") (name "/STLK_NRST") (class "Default")
      (node (ref "C1") (pin "2") (pinfunction "2_2") (pintype "passive"))
      (node (ref "JP1") (pin "1") (pinfunction "COMMON_1") (pintype "passive"))
      (node (ref "U5") (pin "J1") (pinfunction "NRST_J1") (pintype "passive"))
    )
    (net (code "6") (name "/STLK_OSC_IN") (class "Default")
      (node (ref "C33") (pin "2") (pinfunction "2_2") (pintype "passive"))
      (node (ref "U5") (pin "G1") (pinfunction "OSC_IN/PH0_G1") (pintype "passive"))
      (node (ref "X1") (pin "1") (pinfunction "1_1") (pintype "passive"))
    )
    (net (code "7") (name "/STLK_OSC_OUT") (class "Default")
      (node (ref "C32") (pin "2") (pinfunction "2_2") (pintype "passive"))
      (node (ref "U5") (pin "H1") (pinfunction "OSC_OUT/PH1_H1") (pintype "passive"))
      (node (ref "X1") (pin "3") (pinfunction "3_3") (pintype "passive"))
    )
    (net (code "8") (name "/STLK_SWCLK") (class "Default")
      (node (ref "CN2") (pin "2") (pinfunction "2_2") (pintype "passive"))
      (node (ref "U5") (pin "A14") (pinfunction "STLK_SWCLK/PA14_A14") (pintype "passive"))
    )
    (net (code "9") (name "/STLK_SWDIO") (class "Default")
      (node (ref "CN2") (pin "4") (pinfunction "4_4") (pintype "passive"))
      (node (ref "U5") (pin "A15") (pinfunction "STLK_SWDIO/PA13_A15") (pintype "passive"))
    )
    (net (code "10") (name "/STLK_UCPD_CC1_C") (class "Default")
      (node (ref "C3") (pin "1") (pinfunction "1_1") (pintype "passive"))
      (node (ref "R13") (pin "2") (pinfunction "2_2") (pintype "passive"))
      (node (ref "U5") (pin "M5") (pinfunction "ADCx_IN13/PC3_M5") (pintype "passive"))
    )
    (net (code "11") (name "/STLK_UCPD_CC2_C") (class "Default")
      (node (ref "C20") (pin "1") (pinfunction "1_1") (pintype "passive"))
      (node (ref "R14") (pin "2") (pinfunction "2_2") (pintype "passive"))
      (node (ref "U5") (pin "N5") (pinfunction "ADCx_IN14/PC4_N5") (pintype "passive"))
    )
    (net (code "12") (name "/STLK_USB_CN_N") (class "Default")
      (node (ref "CN1") (pin "A7") (pinfunction "D-1_A7") (pintype "passive"))
      (node (ref "CN1") (pin "B7") (pinfunction "D-2_B7") (pintype "passive"))
      (node (ref "U2") (pin "2") (pinfunction "D-_2") (pintype "passive"))
    )
    (net (code "13") (name "/STLK_USB_CN_P") (class "Default")
      (node (ref "CN1") (pin "A6") (pinfunction "D+1_A6") (pintype "passive"))
      (node (ref "CN1") (pin "B6") (pinfunction "D+2_B6") (pintype "passive"))
      (node (ref "U2") (pin "1") (pinfunction "D+_1") (pintype "passive"))
    )
    (net (code "14") (name "/STLK_USB_N") (class "Default")
      (node (ref "U2") (pin "5") (pinfunction "D-_5") (pintype "passive"))
      (node (ref "U5") (pin "R14") (pinfunction "USB_DEV_HS_N/PB14_R14") (pintype "passive"))
    )
    (net (code "15") (name "/STLK_USB_P") (class "Default")
      (node (ref "U2") (pin "6") (pinfunction "D+_6") (pintype "passive"))
      (node (ref "U5") (pin "R15") (pinfunction "USB_DEV_HS_P/PB15_R15") (pintype "passive"))
    )
    (net (code "16") (name "/STLK_VCP_RX") (class "Default")
      (node (ref "R48") (pin "1") (pinfunction "1_1") (pintype "passive"))
      (node (ref "U5") (pin "C10") (pinfunction "STLK_VCP_RX/PG9_C10") (pintype "passive"))
    )
    (net (code "17") (name "/STLK_VCP_TX") (class "Default")
      (node (ref "R49") (pin "1") (pinfunction "1_1") (pintype "passive"))
      (node (ref "U5") (pin "A7") (pinfunction "STLK_VCP_TX/PG14_A7") (pintype "passive"))
    )
    (net (code "18") (name "/T_JTDI") (class "Default")
      (node (ref "CN4") (pin "10") (pinfunction "10_10") (pintype "passive"))
      (node (ref "R47") (pin "2") (pinfunction "2_2") (pintype "passive"))
      (node (ref "U6") (pin "4") (pinfunction "IO3_4") (pintype "passive"))
    )
    (net (code "19") (name "/T_NRST") (class "Default")
      (node (ref "CN4") (pin "12") (pinfunction "12_12") (pintype "passive"))
      (node (ref "R50") (pin "2") (pinfunction "2_2") (pintype "passive"))
      (node (ref "U1") (pin "5") (pinfunction "IO4_5") (pintype "passive"))
    )
    (net (code "20") (name "/T_PWR_EN") (class "Default")
      (node (ref "R54") (pin "2") (pinfunction "2_2") (pintype "passive"))
      (node (ref "R8") (pin "2") (pinfunction "2_2") (pintype "passive"))
      (node (ref "U19") (pin "2") (pinfunction "EN/UVLO_2") (pintype "passive"))
      (node (ref "U4") (pin "4") (pinfunction "EN_4") (pintype "passive"))
      (node (ref "U5") (pin "R5") (pinfunction "T_PWR_EN/PB0_R5") (pintype "passive"))
    )
    (net (code "21") (name "/T_PWR_EXT") (class "Default")
      (node (ref "R11") (pin "1") (pinfunction "1_1") (pintype "passive"))
      (node (ref "R12") (pin "1") (pinfunction "1_1") (pintype "passive"))
      (node (ref "U5") (pin "R4") (pinfunction "T_PWR_EXT/PB1_R4") (pintype "passive"))
    )
    (net (code "22") (name "/T_PWR_INT") (class "Default")
      (node (ref "R18") (pin "2") (pinfunction "2_2") (pintype "passive"))
      (node (ref "R51") (pin "2") (pinfunction "2_2") (pintype "passive"))
      (node (ref "U5") (pin "B13") (pinfunction "T_PWR_INT/PC11_B13") (pintype "passive"))
    )
    (net (code "23") (name "/T_PWR_LED") (class "Default")
      (node (ref "R23") (pin "2") (pinfunction "2_2") (pintype "passive"))
      (node (ref "R24") (pin "2") (pinfunction "2_2") (pintype "passive"))
      (node (ref "U5") (pin "H15") (pinfunction "T_PWR_LED/PC6_H15") (pintype "passive"))
    )
    (net (code "24") (name "/T_PWR_SEL1") (class "Default")
      (node (ref "R20") (pin "2") (pinfunction "2_2") (pintype "passive"))
      (node (ref "U5") (pin "D10") (pinfunction "T_PWR_SEL1/PD4_D10") (pintype "passive"))
    )
    (net (code "25") (name "/T_PWR_SEL2") (class "Default")
      (node (ref "R21") (pin "2") (pinfunction "2_2") (pintype "passive"))
      (node (ref "U5") (pin "C11") (pinfunction "T_PWR_SEL2/PD5_C11") (pintype "passive"))
    )
    (net (code "26") (name "/T_SWCLK") (class "Default")
      (node (ref "CN4") (pin "6") (pinfunction "6_6") (pintype "passive"))
      (node (ref "R44") (pin "2") (pinfunction "2_2") (pintype "passive"))
      (node (ref "U6") (pin "1") (pinfunction "IO1_1") (pintype "passive"))
    )
    (net (code "27") (name "/T_SWDIO") (class "Default")
      (node (ref "CN4") (pin "4") (pinfunction "4_4") (pintype "passive"))
      (node (ref "R45") (pin "2") (pinfunction "2_2") (pintype "passive"))
      (node (ref "U6") (pin "5") (pinfunction "IO4_5") (pintype "passive"))
    )
    (net (code "28") (name "/T_SWO") (class "Default")
      (node (ref "CN4") (pin "8") (pinfunction "8_8") (pintype "passive"))
      (node (ref "R46") (pin "2") (pinfunction "2_2") (pintype "passive"))
      (node (ref "U6") (pin "3") (pinfunction "IO2_3") (pintype "passive"))
    )
    (net (code "29") (name "/T_VCC_AIN") (class "Default")
      (node (ref "R16") (pin "1") (pinfunction "1_1") (pintype "passive"))
      (node (ref "R19") (pin "1") (pinfunction "1_1") (pintype "passive"))
      (node (ref "U5") (pin "N3") (pinfunction "T_VCC_AIN/PA0_N3") (pintype "passive"))
    )
    (net (code "30") (name "/T_VCP_RX") (class "Default")
      (node (ref "CN4") (pin "13") (pinfunction "13_13") (pintype "passive"))
      (node (ref "R49") (pin "2") (pinfunction "2_2") (pintype "passive"))
      (node (ref "U1") (pin "3") (pinfunction "IO2_3") (pintype "passive"))
    )
    (net (code "31") (name "/T_VCP_TX") (class "Default")
      (node (ref "CN4") (pin "14") (pinfunction "14_14") (pintype "passive"))
      (node (ref "R48") (pin "2") (pinfunction "2_2") (pintype "passive"))
      (node (ref "U1") (pin "1") (pinfunction "IO1_1") (pintype "passive"))
    )
    (net (code "32") (name "3V3") (class "Default")
      (node (ref "CN4") (pin "3") (pinfunction "3_3") (pintype "passive"))
      (node (ref "R19") (pin "2") (pinfunction "2_2") (pintype "passive"))
    )
    (net (code "33") (name "3V3_STLK") (class "Default")
      (node (ref "C13") (pin "1") (pinfunction "1_1") (pintype "passive"))
      (node (ref "C14") (pin "1") (pinfunction "1_1") (pintype "passive"))
      (node (ref "C15") (pin "1") (pinfunction "1_1") (pintype "passive"))
      (node (ref "C16") (pin "1") (pinfunction "1_1") (pintype "passive"))
      (node (ref "C17") (pin "1") (pinfunction "1_1") (pintype "passive"))
      (node (ref "C18") (pin "1") (pinfunction "1_1") (pintype "passive"))
      (node (ref "C21") (pin "1") (pinfunction "1_1") (pintype "passive"))
      (node (ref "C22") (pin "1") (pinfunction "1_1") (pintype "passive"))
      (node (ref "C23") (pin "1") (pinfunction "1_1") (pintype "passive"))
      (node (ref "C24") (pin "1") (pinfunction "1_1") (pintype "passive"))
      (node (ref "C25") (pin "1") (pinfunction "1_1") (pintype "passive"))
      (node (ref "C26") (pin "1") (pinfunction "1_1") (pintype "passive"))
      (node (ref "C27") (pin "1") (pinfunction "1_1") (pintype "passive"))
      (node (ref "C31") (pin "2") (pinfunction "2_2") (pintype "passive"))
      (node (ref "C6") (pin "1") (pinfunction "1_1") (pintype "passive"))
      (node (ref "C7") (pin "1") (pinfunction "1_1") (pintype "passive"))
      (node (ref "C8") (pin "1") (pinfunction "1_1") (pintype "passive"))
      (node (ref "C9") (pin "1") (pinfunction "1_1") (pintype "passive"))
      (node (ref "CN2") (pin "1") (pinfunction "1_1") (pintype "passive"))
      (node (ref "LD1") (pin "4") (pinfunction "Green_anode_4") (pintype "passive"))
      (node (ref "LD7") (pin "4") (pinfunction "Green_anode_4") (pintype "passive"))
      (node (ref "R10") (pin "2") (pinfunction "2_2") (pintype "passive"))
      (node (ref "U5") (pin "C1") (pinfunction "VBAT_C1") (pintype "passive"))
      (node (ref "U5") (pin "C5") (pinfunction "VDD_C5") (pintype "passive"))
      (node (ref "U5") (pin "C6") (pinfunction "PDR_ON_C6") (pintype "passive"))
      (node (ref "U5") (pin "C7") (pinfunction "VDD_C7") (pintype "passive"))
      (node (ref "U5") (pin "C8") (pinfunction "VDD_C8") (pintype "passive"))
      (node (ref "U5") (pin "C9") (pinfunction "VDD_C9") (pintype "passive"))
      (node (ref "U5") (pin "F3") (pinfunction "VDD_F3") (pintype "passive"))
      (node (ref "U5") (pin "G13") (pinfunction "VDD_G13") (pintype "passive"))
      (node (ref "U5") (pin "G3") (pinfunction "VDD_G3") (pintype "passive"))
      (node (ref "U5") (pin "H13") (pinfunction "VDD_H13") (pintype "passive"))
      (node (ref "U5") (pin "J12") (pinfunction "VDD_J12") (pintype "passive"))
      (node (ref "U5") (pin "J13") (pinfunction "VDD_J13") (pintype "passive"))
      (node (ref "U5") (pin "K4") (pinfunction "VDD_K4") (pintype "passive"))
      (node (ref "U5") (pin "N10") (pinfunction "VDD_N10") (pintype "passive"))
      (node (ref "U5") (pin "N8") (pinfunction "VDD_N8") (pintype "passive"))
      (node (ref "U5") (pin "N9") (pinfunction "VDD_N9") (pintype "passive"))
      (node (ref "U5") (pin "P1") (pinfunction "VREF+_P1") (pintype "passive"))
      (node (ref "U5") (pin "R1") (pinfunction "VDDA_R1") (pintype "passive"))
      (node (ref "U7") (pin "1") (pinfunction "VOUT_1") (pintype "passive"))
    )
    (net (code "34") (name "5V") (class "Default")
      (node (ref "R11") (pin "2") (pinfunction "2_2") (pintype "passive"))
    )
    (net (code "35") (name "5V_STLK") (class "Default")
      (node (ref "C28") (pin "2") (pinfunction "2_2") (pintype "passive"))
      (node (ref "C5") (pin "2") (pinfunction "2_2") (pintype "passive"))
      (node (ref "U19") (pin "5") (pinfunction "OUT_5") (pintype "passive"))
      (node (ref "U4") (pin "1") (pinfunction "OUT_1") (pintype "passive"))
    )
    (net (code "36") (name "5V_VIN") (class "Default")
      (node (ref "D2") (pin "1") (pinfunction "A_1") (pintype "passive"))
    )
    (net (code "37") (name "E5V") (class "Default")
      (node (ref "D4") (pin "1") (pinfunction "A_1") (pintype "passive"))
    )
    (net (code "38") (name "GND") (class "Default")
      (node (ref "C1") (pin "1") (pinfunction "1_1") (pintype "passive"))
      (node (ref "C10") (pin "1") (pinfunction "1_1") (pintype "passive"))
      (node (ref "C11") (pin "1") (pinfunction "1_1") (pintype "passive"))
      (node (ref "C12") (pin "1") (pinfunction "1_1") (pintype "passive"))
      (node (ref "C13") (pin "2") (pinfunction "2_2") (pintype "passive"))
      (node (ref "C14") (pin "2") (pinfunction "2_2") (pintype "passive"))
      (node (ref "C15") (pin "2") (pinfunction "2_2") (pintype "passive"))
      (node (ref "C16") (pin "2") (pinfunction "2_2") (pintype "passive"))
      (node (ref "C17") (pin "2") (pinfunction "2_2") (pintype "passive"))
      (node (ref "C18") (pin "2") (pinfunction "2_2") (pintype "passive"))
      (node (ref "C19") (pin "1") (pinfunction "1_1") (pintype "passive"))
      (node (ref "C2") (pin "2") (pinfunction "2_2") (pintype "passive"))
      (node (ref "C20") (pin "2") (pinfunction "2_2") (pintype "passive"))
      (node (ref "C21") (pin "2") (pinfunction "2_2") (pintype "passive"))
      (node (ref "C22") (pin "2") (pinfunction "2_2") (pintype "passive"))
      (node (ref "C23") (pin "2") (pinfunction "2_2") (pintype "passive"))
      (node (ref "C24") (pin "2") (pinfunction "2_2") (pintype "passive"))
      (node (ref "C25") (pin "2") (pinfunction "2_2") (pintype "passive"))
      (node (ref "C26") (pin "2") (pinfunction "2_2") (pintype "passive"))
      (node (ref "C27") (pin "2") (pinfunction "2_2") (pintype "passive"))
      (node (ref "C28") (pin "1") (pinfunction "1_1") (pintype "passive"))
      (node (ref "C29") (pin "1") (pinfunction "1_1") (pintype "passive"))
      (node (ref "C3") (pin "2") (pinfunction "2_2") (pintype "passive"))
      (node (ref "C30") (pin "1") (pinfunction "1_1") (pintype "passive"))
      (node (ref "C31") (pin "1") (pinfunction "1_1") (pintype "passive"))
      (node (ref "C32") (pin "1") (pinfunction "1_1") (pintype "passive"))
      (node (ref "C33") (pin "1") (pinfunction "1_1") (pintype "passive"))
      (node (ref "C4") (pin "1") (pinfunction "1_1") (pintype "passive"))
      (node (ref "C46") (pin "1") (pinfunction "1_1") (pintype "passive"))
      (node (ref "C5") (pin "1") (pinfunction "1_1") (pintype "passive"))
      (node (ref "C6") (pin "2") (pinfunction "2_2") (pintype "passive"))
      (node (ref "C7") (pin "2") (pinfunction "2_2") (pintype "passive"))
      (node (ref "C8") (pin "2") (pinfunction "2_2") (pintype "passive"))
      (node (ref "C9") (pin "2") (pinfunction "2_2") (pintype "passive"))
      (node (ref "CN1") (pin "A1") (pinfunction "GND1_A1") (pintype "passive"))
      (node (ref "CN1") (pin "A12") (pinfunction "GND2_A12") (pintype "passive"))
      (node (ref "CN1") (pin "B1") (pinfunction "GND3_B1") (pintype "passive"))
      (node (ref "CN1") (pin "B12") (pinfunction "GND4_B12") (pintype "passive"))
      (node (ref "CN1") (pin "SH1") (pinfunction "Shield1_SH1") (pintype "passive"))
      (node (ref "CN1") (pin "SH2") (pinfunction "Shield2_SH2") (pintype "passive"))
      (node (ref "CN1") (pin "SH3") (pinfunction "Shield3_SH3") (pintype "passive"))
      (node (ref "CN1") (pin "SH4") (pinfunction "Shield4_SH4") (pintype "passive"))
      (node (ref "CN2") (pin "3") (pinfunction "3_3") (pintype "passive"))
      (node (ref "CN4") (pin "5") (pinfunction "5_5") (pintype "passive"))
      (node (ref "CN4") (pin "7") (pinfunction "7_7") (pintype "passive"))
      (node (ref "JP1") (pin "2") (pinfunction "NO_2") (pintype "passive"))
      (node (ref "LD1") (pin "3") (pinfunction "RED_cathode_3") (pintype "passive"))
      (node (ref "LD7") (pin "3") (pinfunction "RED_cathode_3") (pintype "passive"))
      (node (ref "R12") (pin "2") (pinfunction "2_2") (pintype "passive"))
      (node (ref "R15") (pin "1") (pinfunction "1_1") (pintype "passive"))
      (node (ref "R16") (pin "2") (pinfunction "2_2") (pintype "passive"))
      (node (ref "R17") (pin "2") (pinfunction "2_2") (pintype "passive"))
      (node (ref "R18") (pin "1") (pinfunction "1_1") (pintype "passive"))
      (node (ref "R22") (pin "2") (pinfunction "2_2") (pintype "passive"))
      (node (ref "R5") (pin "2") (pinfunction "2_2") (pintype "passive"))
      (node (ref "R54") (pin "1") (pinfunction "1_1") (pintype "passive"))
      (node (ref "R8") (pin "1") (pinfunction "1_1") (pintype "passive"))
      (node (ref "R9") (pin "2") (pinfunction "2_2") (pintype "passive"))
      (node (ref "U1") (pin "2") (pinfunction "GND_2") (pintype "passive"))
      (node (ref "U19") (pin "8") (pinfunction "GND_8") (pintype "passive"))
      (node (ref "U19") (pin "9") (pinfunction "EP_9") (pintype "passive"))
      (node (ref "U2") (pin "3") (pinfunction "GND_3") (pintype "passive"))
      (node (ref "U3") (pin "2") (pinfunction "GND_2") (pintype "passive"))
      (node (ref "U4") (pin "2") (pinfunction "GND_2") (pintype "passive"))
      (node (ref "U5") (pin "D5") (pinfunction "VSS_D5") (pintype "passive"))
      (node (ref "U5") (pin "D6") (pinfunction "BOOT0_D6") (pintype "passive"))
      (node (ref "U5") (pin "D7") (pinfunction "VSS_D7") (pintype "passive"))
      (node (ref "U5") (pin "D8") (pinfunction "VSS_D8") (pintype "passive"))
      (node (ref "U5") (pin "D9") (pinfunction "VSS_D9") (pintype "passive"))
      (node (ref "U5") (pin "F10") (pinfunction "VSS_F10") (pintype "passive"))
      (node (ref "U5") (pin "F12") (pinfunction "VSS_F12") (pintype "passive"))
      (node (ref "U5") (pin "F2") (pinfunction "VSS_F2") (pintype "passive"))
      (node (ref "U5") (pin "F6") (pinfunction "VSS_F6") (pintype "passive"))
      (node (ref "U5") (pin "F7") (pinfunction "VSS_F7") (pintype "passive"))
      (node (ref "U5") (pin "F8") (pinfunction "VSS_F8") (pintype "passive"))
      (node (ref "U5") (pin "F9") (pinfunction "VSS_F9") (pintype "passive"))
      (node (ref "U5") (pin "G10") (pinfunction "VSS_G10") (pintype "passive"))
      (node (ref "U5") (pin "G12") (pinfunction "VSS_G12") (pintype "passive"))
      (node (ref "U5") (pin "G2") (pinfunction "VSS_G2") (pintype "passive"))
      (node (ref "U5") (pin "G6") (pinfunction "VSS_G6") (pintype "passive"))
      (node (ref "U5") (pin "G7") (pinfunction "VSS_G7") (pintype "passive"))
      (node (ref "U5") (pin "G8") (pinfunction "VSS_G8") (pintype "passive"))
      (node (ref "U5") (pin "G9") (pinfunction "VSS_G9") (pintype "passive"))
      (node (ref "U5") (pin "H10") (pinfunction "VSS_H10") (pintype "passive"))
      (node (ref "U5") (pin "H12") (pinfunction "VSS_H12") (pintype "passive"))
      (node (ref "U5") (pin "H6") (pinfunction "VSS_H6") (pintype "passive"))
      (node (ref "U5") (pin "H7") (pinfunction "VSS_H7") (pintype "passive"))
      (node (ref "U5") (pin "H8") (pinfunction "VSS_H8") (pintype "passive"))
      (node (ref "U5") (pin "H9") (pinfunction "VSS_H9") (pintype "passive"))
      (node (ref "U5") (pin "J10") (pinfunction "VSS_J10") (pintype "passive"))
      (node (ref "U5") (pin "J6") (pinfunction "VSS_J6") (pintype "passive"))
      (node (ref "U5") (pin "J7") (pinfunction "VSS_J7") (pintype "passive"))
      (node (ref "U5") (pin "J8") (pinfunction "VSS_J8") (pintype "passive"))
      (node (ref "U5") (pin "J9") (pinfunction "VSS_J9") (pintype "passive"))
      (node (ref "U5") (pin "K10") (pinfunction "VSS_K10") (pintype "passive"))
      (node (ref "U5") (pin "K6") (pinfunction "VSS_K6") (pintype "passive"))
      (node (ref "U5") (pin "K7") (pinfunction "VSS_K7") (pintype "passive"))
      (node (ref "U5") (pin "K8") (pinfunction "VSS_K8") (pintype "passive"))
      (node (ref "U5") (pin "K9") (pinfunction "VSS_K9") (pintype "passive"))
      (node (ref "U5") (pin "L4") (pinfunction "BYPASS-REG_L4") (pintype "passive"))
      (node (ref "U5") (pin "M1") (pinfunction "VSSA_M1") (pintype "passive"))
      (node (ref "U5") (pin "M8") (pinfunction "VSS_M8") (pintype "passive"))
      (node (ref "U5") (pin "M9") (pinfunction "VSS_M9") (pintype "passive"))
      (node (ref "U5") (pin "N1") (pinfunction "VREF-_N1") (pintype "passive"))
      (node (ref "U6") (pin "2") (pinfunction "GND_2") (pintype "passive"))
      (node (ref "U7") (pin "2") (pinfunction "GND_2") (pintype "passive"))
      (node (ref "X1") (pin "2") (pinfunction "2_2") (pintype "passive"))
      (node (ref "X1") (pin "4") (pinfunction "4_4") (pintype "passive"))
    )
    (net (code "39") (name "Net-(CN1-CC1)") (class "Default")
      (node (ref "CN1") (pin "A5") (pinfunction "CC1_A5") (pintype "passive"))
      (node (ref "R13") (pin "1") (pinfunction "1_1") (pintype "passive"))
      (node (ref "R9") (pin "1") (pinfunction "1_1") (pintype "passive"))
    )
    (net (code "40") (name "Net-(CN1-CC2)") (class "Default")
      (node (ref "CN1") (pin "B5") (pinfunction "CC2_B5") (pintype "passive"))
      (node (ref "R14") (pin "1") (pinfunction "1_1") (pintype "passive"))
      (node (ref "R17") (pin "1") (pinfunction "1_1") (pintype "passive"))
    )
    (net (code "41") (name "Net-(D1-K)") (class "Default")
      (node (ref "C19") (pin "2") (pinfunction "2_2") (pintype "passive"))
      (node (ref "D1") (pin "2") (pinfunction "K_2") (pintype "passive"))
      (node (ref "D2") (pin "2") (pinfunction "K_2") (pintype "passive"))
      (node (ref "D3") (pin "2") (pinfunction "K_2") (pintype "passive"))
      (node (ref "D4") (pin "2") (pinfunction "K_2") (pintype "passive"))
      (node (ref "U7") (pin "3") (pinfunction "VIN_3") (pintype "passive"))
      (node (ref "U7") (pin "5") (pinfunction "EN_5") (pintype "passive"))
    )
    (net (code "42") (name "Net-(LD1-Green_cathode)") (class "Default")
      (node (ref "LD1") (pin "2") (pinfunction "Green_cathode_2") (pintype "passive"))
      (node (ref "R2") (pin "2") (pinfunction "2_2") (pintype "passive"))
    )
    (net (code "43") (name "Net-(LD1-Red_anode)") (class "Default")
      (node (ref "LD1") (pin "1") (pinfunction "Red_anode_1") (pintype "passive"))
      (node (ref "R3") (pin "1") (pinfunction "1_1") (pintype "passive"))
    )
    (net (code "44") (name "Net-(LD4-Pad1)") (class "Default")
      (node (ref "LD4") (pin "1") (pintype "passive"))
      (node (ref "R1") (pin "1") (pinfunction "1_1") (pintype "passive"))
    )
    (net (code "45") (name "Net-(LD7-Green_cathode)") (class "Default")
      (node (ref "LD7") (pin "2") (pinfunction "Green_cathode_2") (pintype "passive"))
      (node (ref "R24") (pin "1") (pinfunction "1_1") (pintype "passive"))
    )
    (net (code "46") (name "Net-(LD7-Red_anode)") (class "Default")
      (node (ref "LD7") (pin "1") (pinfunction "Red_anode_1") (pintype "passive"))
      (node (ref "R23") (pin "1") (pinfunction "1_1") (pintype "passive"))
    )
    (net (code "47") (name "Net-(U4-~{FAULT})") (class "Default")
      (node (ref "LD4") (pin "2") (pintype "passive"))
      (node (ref "R6") (pin "1") (pinfunction "1_1") (pintype "passive"))
      (node (ref "U4") (pin "3") (pinfunction "~{FAULT}_3") (pintype "passive"))
    )
    (net (code "48") (name "Net-(U5A-HW_TYP_0{slash}PI4)") (class "Default")
      (node (ref "R10") (pin "1") (pinfunction "1_1") (pintype "passive"))
      (node (ref "U5") (pin "D4") (pinfunction "HW_TYP_0/PI4_D4") (pintype "passive"))
    )
    (net (code "49") (name "Net-(U5A-REXT_OTGPHY)") (class "Default")
      (node (ref "R5") (pin "1") (pinfunction "1_1") (pintype "passive"))
      (node (ref "U5") (pin "J15") (pinfunction "REXT_OTGPHY_J15") (pintype "passive"))
    )
    (net (code "50") (name "Net-(U5A-T_JCLK_OUT{slash}PB2)") (class "Default")
      (node (ref "R44") (pin "1") (pinfunction "1_1") (pintype "passive"))
      (node (ref "U5") (pin "A10") (pinfunction "T_JRCLK/PB3_A10") (pintype "passive"))
      (node (ref "U5") (pin "M11") (pinfunction "T_SWCLK/PH6_M11") (pintype "passive"))
      (node (ref "U5") (pin "M6") (pinfunction "T_JCLK_OUT/PB2_M6") (pintype "passive"))
    )
    (net (code "51") (name "Net-(U5A-T_JTDO{slash}PB5)") (class "Default")
      (node (ref "R46") (pin "1") (pinfunction "1_1") (pintype "passive"))
      (node (ref "U5") (pin "A6") (pinfunction "T_JTDO/PB5_A6") (pintype "passive"))
      (node (ref "U5") (pin "D12") (pinfunction "T_SWO/PD2_D12") (pintype "passive"))
    )
    (net (code "52") (name "Net-(U5A-T_JTMS{slash}T_SWDIO_OUT{slash}PF9)") (class "Default")
      (node (ref "R45") (pin "1") (pinfunction "1_1") (pintype "passive"))
      (node (ref "U5") (pin "L2") (pinfunction "T_JTMS/T_SWDIO_OUT/PF9_L2") (pintype "passive"))
      (node (ref "U5") (pin "N12") (pinfunction "T_SWDIO_IN/PH7_N12") (pintype "passive"))
    )
    (net (code "53") (name "Net-(U5A-T_MCO{slash}PA8)") (class "Default")
      (node (ref "R4") (pin "1") (pinfunction "1_1") (pintype "passive"))
      (node (ref "U5") (pin "F15") (pinfunction "T_MCO/PA8_F15") (pintype "passive"))
    )
    (net (code "54") (name "Net-(U5A-T_NRST{slash}PA6)") (class "Default")
      (node (ref "R50") (pin "1") (pinfunction "1_1") (pintype "passive"))
      (node (ref "U5") (pin "P3") (pinfunction "T_NRST/PA6_P3") (pintype "passive"))
    )
    (net (code "55") (name "Net-(U5A-V12_OTGPHY)") (class "Default")
      (node (ref "C4") (pin "2") (pinfunction "2_2") (pintype "passive"))
      (node (ref "U5") (pin "J14") (pinfunction "V12_OTGPHY_J14") (pintype "passive"))
    )
    (net (code "56") (name "Net-(U5B-VCAP1)") (class "Default")
      (node (ref "C12") (pin "2") (pinfunction "2_2") (pintype "passive"))
      (node (ref "U5") (pin "M10") (pinfunction "VCAP1_M10") (pintype "passive"))
    )
    (net (code "57") (name "Net-(U5B-VCAP2)") (class "Default")
      (node (ref "C10") (pin "2") (pinfunction "2_2") (pintype "passive"))
      (node (ref "U5") (pin "F13") (pinfunction "VCAP2_F13") (pintype "passive"))
    )
    (net (code "58") (name "Net-(U19-ILM)") (class "Default")
      (node (ref "R20") (pin "1") (pinfunction "1_1") (pintype "passive"))
      (node (ref "R21") (pin "1") (pinfunction "1_1") (pintype "passive"))
      (node (ref "R22") (pin "1") (pinfunction "1_1") (pintype "passive"))
      (node (ref "U19") (pin "7") (pinfunction "ILM_7") (pintype "passive"))
    )
    (net (code "59") (name "Net-(U19-QOD)") (class "Default")
      (node (ref "R51") (pin "1") (pinfunction "1_1") (pintype "passive"))
      (node (ref "U19") (pin "6") (pinfunction "QOD_6") (pintype "passive"))
    )
    (net (code "60") (name "Net-(U19-dVdt)") (class "Default")
      (node (ref "C30") (pin "2") (pinfunction "2_2") (pintype "passive"))
      (node (ref "U19") (pin "1") (pinfunction "dVdt_1") (pintype "passive"))
    )
    (net (code "61") (name "VBUS_STLK") (class "Default")
      (node (ref "C11") (pin "2") (pinfunction "2_2") (pintype "passive"))
      (node (ref "C2") (pin "1") (pinfunction "1_1") (pintype "passive"))
      (node (ref "C29") (pin "2") (pinfunction "2_2") (pintype "passive"))
      (node (ref "CN1") (pin "A4") (pinfunction "VBUS1_A4") (pintype "passive"))
      (node (ref "CN1") (pin "A9") (pinfunction "VBUS2_A9") (pintype "passive"))
      (node (ref "CN1") (pin "B4") (pinfunction "VBUS3_B4") (pintype "passive"))
      (node (ref "CN1") (pin "B9") (pinfunction "VBUS4_B9") (pintype "passive"))
      (node (ref "D1") (pin "1") (pinfunction "A_1") (pintype "passive"))
      (node (ref "R1") (pin "2") (pinfunction "2_2") (pintype "passive"))
      (node (ref "R6") (pin "2") (pinfunction "2_2") (pintype "passive"))
      (node (ref "U19") (pin "3") (pinfunction "IN_3") (pintype "passive"))
      (node (ref "U19") (pin "4") (pinfunction "IN_4") (pintype "passive"))
      (node (ref "U3") (pin "1") (pinfunction "IO1_1") (pintype "passive"))
      (node (ref "U4") (pin "5") (pinfunction "IN_5") (pintype "passive"))
    )
    (net (code "62") (name "VBUSc") (class "Default")
      (node (ref "D3") (pin "1") (pinfunction "A_1") (pintype "passive"))
    )
    (net (code "63") (name "unconnected-(CN1-RX1+-PadB11)") (class "Default")
      (node (ref "CN1") (pin "B11") (pinfunction "RX1+_B11") (pintype "passive+no_connect"))
    )
    (net (code "64") (name "unconnected-(CN1-RX1--PadB10)") (class "Default")
      (node (ref "CN1") (pin "B10") (pinfunction "RX1-_B10") (pintype "passive+no_connect"))
    )
    (net (code "65") (name "unconnected-(CN1-RX2+-PadA11)") (class "Default")
      (node (ref "CN1") (pin "A11") (pinfunction "RX2+_A11") (pintype "passive+no_connect"))
    )
    (net (code "66") (name "unconnected-(CN1-RX2--PadA10)") (class "Default")
      (node (ref "CN1") (pin "A10") (pinfunction "RX2-_A10") (pintype "passive+no_connect"))
    )
    (net (code "67") (name "unconnected-(CN1-SBU1-PadA8)") (class "Default")
      (node (ref "CN1") (pin "A8") (pinfunction "SBU1_A8") (pintype "passive+no_connect"))
    )
    (net (code "68") (name "unconnected-(CN1-SBU2-PadB8)") (class "Default")
      (node (ref "CN1") (pin "B8") (pinfunction "SBU2_B8") (pintype "passive+no_connect"))
    )
    (net (code "69") (name "unconnected-(CN1-TX1+-PadA2)") (class "Default")
      (node (ref "CN1") (pin "A2") (pinfunction "TX1+_A2") (pintype "passive+no_connect"))
    )
    (net (code "70") (name "unconnected-(CN1-TX1--PadA3)") (class "Default")
      (node (ref "CN1") (pin "A3") (pinfunction "TX1-_A3") (pintype "passive+no_connect"))
    )
    (net (code "71") (name "unconnected-(CN1-TX2+-PadB2)") (class "Default")
      (node (ref "CN1") (pin "B2") (pinfunction "TX2+_B2") (pintype "passive+no_connect"))
    )
    (net (code "72") (name "unconnected-(CN1-TX2--PadB3)") (class "Default")
      (node (ref "CN1") (pin "B3") (pinfunction "TX2-_B3") (pintype "passive+no_connect"))
    )
    (net (code "73") (name "unconnected-(CN4-Pad1)") (class "Default")
      (node (ref "CN4") (pin "1") (pinfunction "1_1") (pintype "passive+no_connect"))
    )
    (net (code "74") (name "unconnected-(CN4-Pad2)") (class "Default")
      (node (ref "CN4") (pin "2") (pinfunction "2_2") (pintype "passive+no_connect"))
    )
    (net (code "75") (name "unconnected-(CN4-Pad9)") (class "Default")
      (node (ref "CN4") (pin "9") (pinfunction "9_9") (pintype "passive+no_connect"))
    )
    (net (code "76") (name "unconnected-(U1-IO3-Pad4)") (class "Default")
      (node (ref "U1") (pin "4") (pinfunction "IO3_4") (pintype "passive+no_connect"))
    )
    (net (code "77") (name "unconnected-(U2-NC-Pad4)") (class "Default")
      (node (ref "U2") (pin "4") (pinfunction "NC_4") (pintype "passive+no_connect"))
    )
    (net (code "78") (name "unconnected-(U5A-GNDDetect{slash}PG5-PadK13)") (class "Default")
      (node (ref "U5") (pin "K13") (pinfunction "GNDDetect/PG5_K13") (pintype "passive+no_connect"))
    )
    (net (code "79") (name "unconnected-(U5A-HW_TYP_1{slash}PI5-PadC4)") (class "Default")
      (node (ref "U5") (pin "C4") (pinfunction "HW_TYP_1/PI5_C4") (pintype "passive+no_connect"))
    )
    (net (code "80") (name "unconnected-(U5A-T_JNRST{slash}PF13-PadN6)") (class "Default")
      (node (ref "U5") (pin "N6") (pinfunction "T_JNRST/PF13_N6") (pintype "passive+no_connect"))
    )
    (net (code "81") (name "unconnected-(U5A-T_SW_DIR{slash}PA7-PadR3)") (class "Default")
      (node (ref "U5") (pin "R3") (pinfunction "T_SW_DIR/PA7_R3") (pintype "passive+no_connect"))
    )
    (net (code "82") (name "unconnected-(U7-NC{slash}ADJ-Pad4)") (class "Default")
      (node (ref "U7") (pin "4") (pinfunction "NC/ADJ_4") (pintype "passive+no_connect"))
    )
  )
)
